# Schematic.net
KiCad netlist of a schematic drawn in Altium Designer
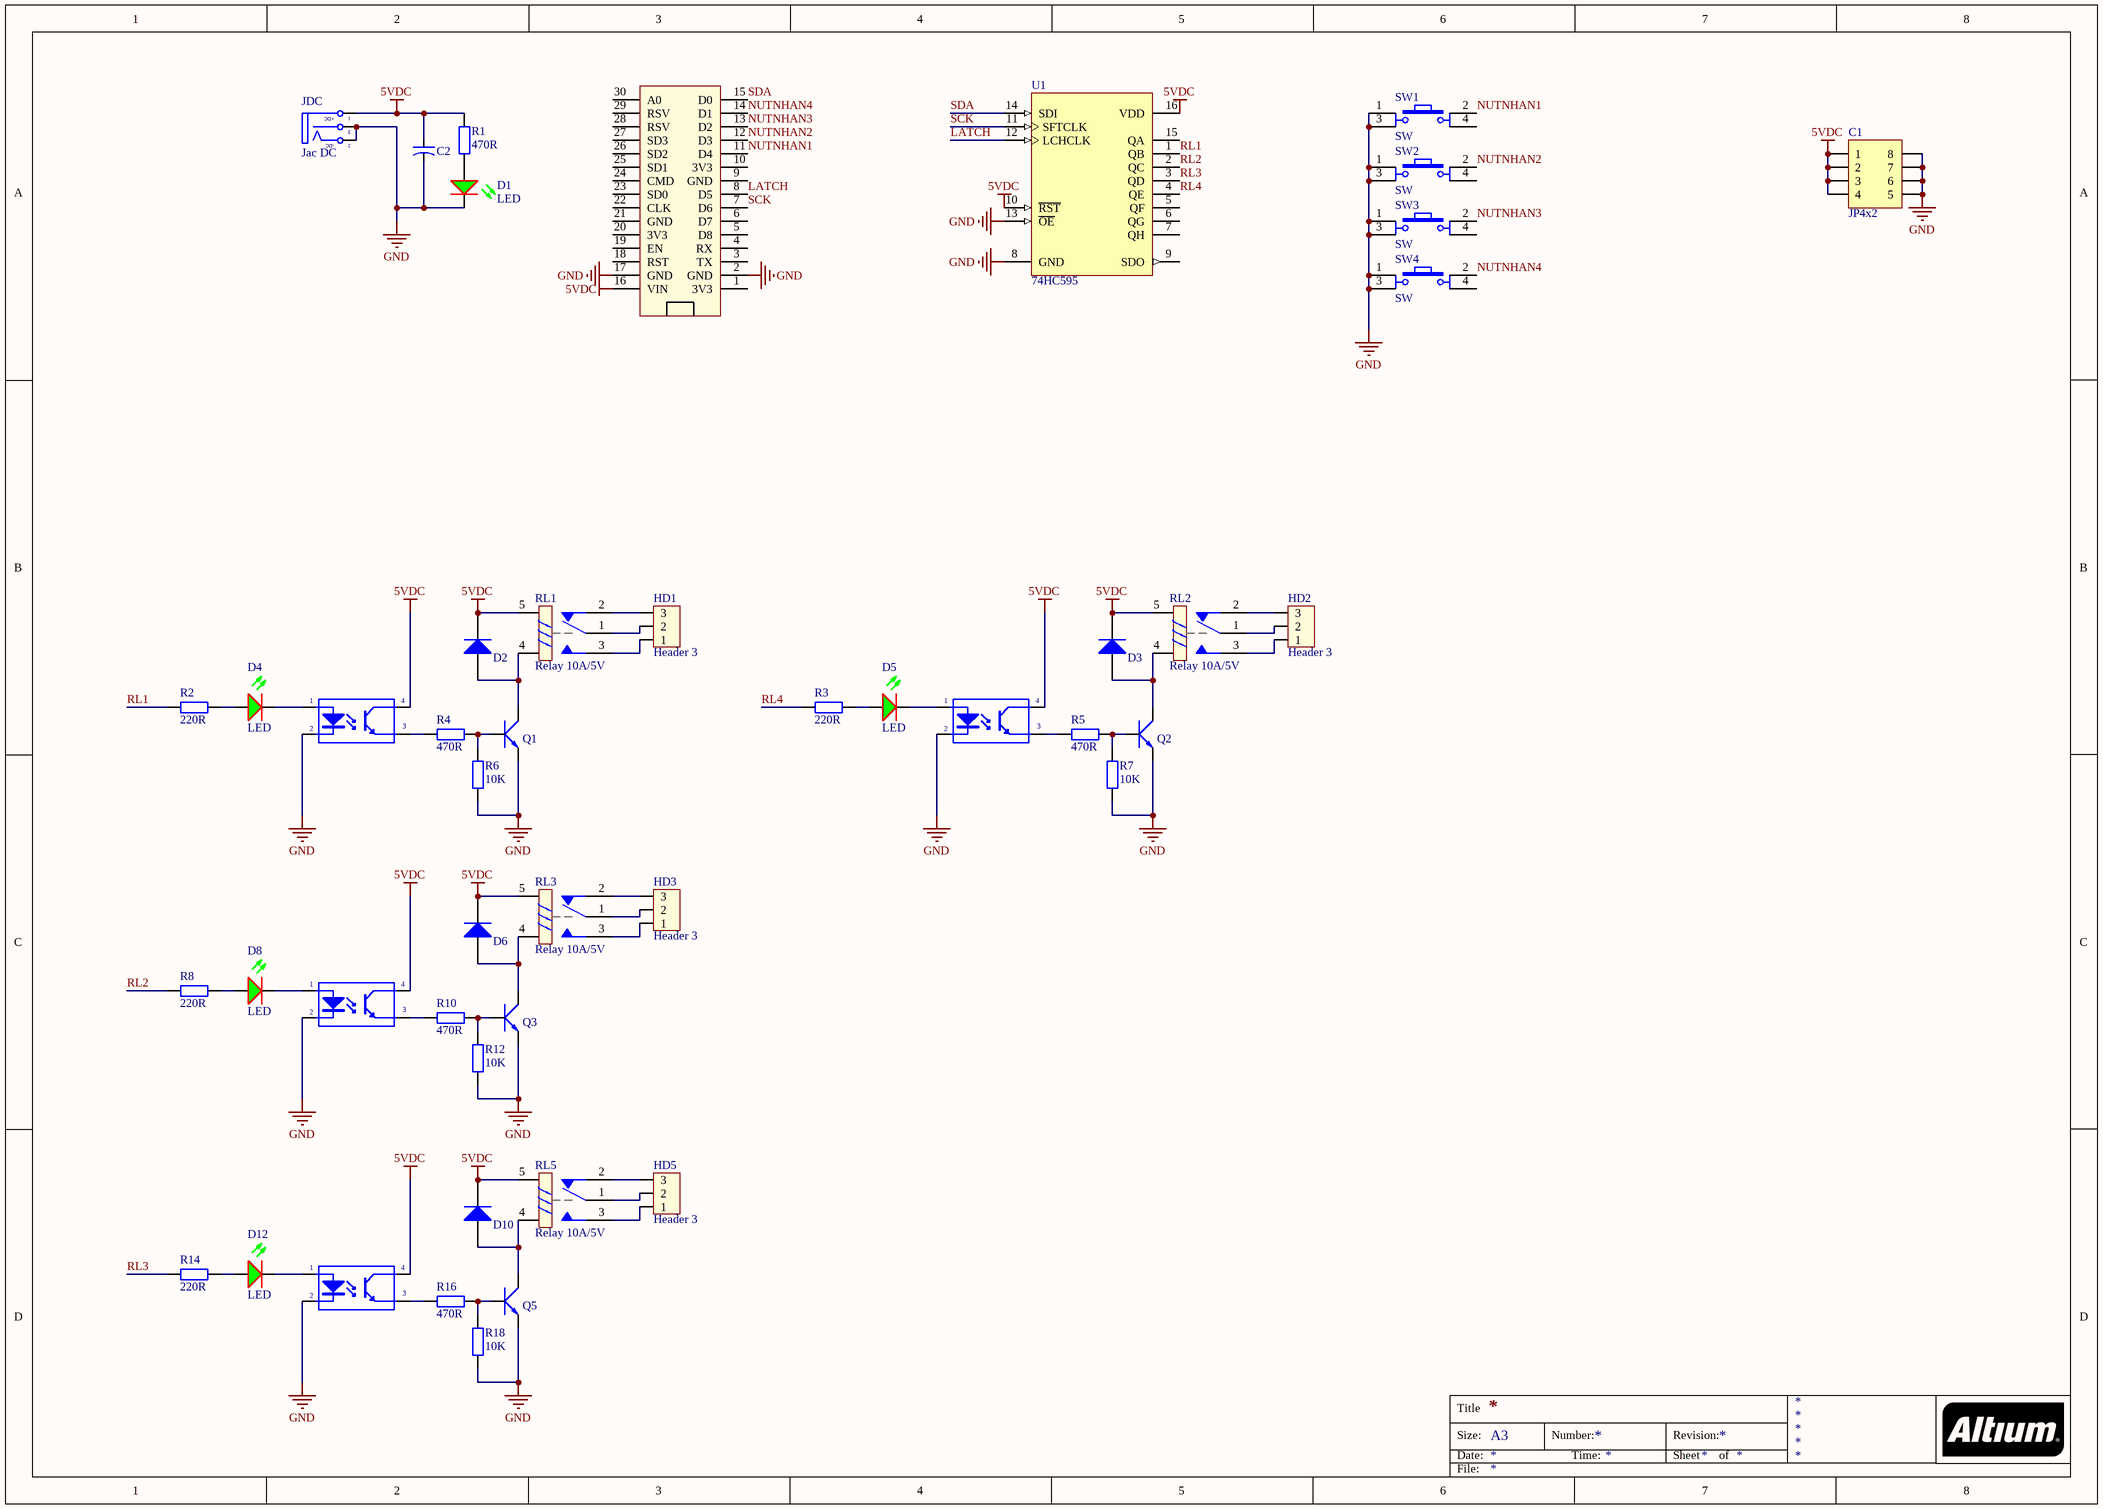
[diagram p0: Schematic.SchDoc]

(export (version "E")
  (design (tool "Eeschema 10.0.6"))
  (components
    (comp (ref "*2")
      (value "Module ESP8266 CP2102")
      (footprint "Module ESP8266 CP2102")
      (libsource (lib "Lib_NTD_HaUI") (part "Module ESP8266 CP2102"))
    )
    (comp (ref "C1")
      (value "JP4x2")
      (footprint "JP4-D2T")
      (description "WR-PHD 2.54 mm Dual Socket Header")
      (fields
        (field (name "MANUFACTURER") "Würth Elektronik eiSos GmbH")
        (field (name "PARTNO") "61300821821")
        (field (name "CREATED BY") "Karrer Zheng")
      )
      (libsource (lib "LIBRARY") (part "JP4x2"))
    )
    (comp (ref "C2")
      (value "10uF")
      (footprint "CA-ALU-2.54")
      (description "Capacitor (Semiconductor SIM Model)")
      (fields (field (name "PUBLISHER") "Altium Limited"))
      (libsource (lib "LIBRARY") (part "CN-ALU-DIP"))
    )
    (comp (ref "D1")
      (value "LED")
      (footprint "LED_SMD_0805")
      (libsource (lib "AltiumLibraryTieuBao") (part "LED"))
    )
    (comp (ref "D2") (value "DIODE") (footprint "DO 214AC") (libsource (lib "Lib_NTD_HaUI") (part "DIODE")))
    (comp (ref "D3") (value "DIODE") (footprint "DO 214AC") (libsource (lib "Lib_NTD_HaUI") (part "DIODE")))
    (comp (ref "D4")
      (value "LED")
      (footprint "LED_SMD_0805")
      (libsource (lib "AltiumLibraryTieuBao") (part "LED"))
    )
    (comp (ref "D5")
      (value "LED")
      (footprint "LED_SMD_0805")
      (libsource (lib "AltiumLibraryTieuBao") (part "LED"))
    )
    (comp (ref "D6") (value "DIODE") (footprint "DO 214AC") (libsource (lib "Lib_NTD_HaUI") (part "DIODE")))
    (comp (ref "D8")
      (value "LED")
      (footprint "LED_SMD_0805")
      (libsource (lib "AltiumLibraryTieuBao") (part "LED"))
    )
    (comp (ref "D10") (value "DIODE") (footprint "DO 214AC") (libsource (lib "Lib_NTD_HaUI") (part "DIODE")))
    (comp (ref "D12")
      (value "LED")
      (footprint "LED_SMD_0805")
      (libsource (lib "AltiumLibraryTieuBao") (part "LED"))
    )
    (comp (ref "HD1")
      (value "Header 3")
      (footprint "HED3")
      (description "Header 3 (Green)")
      (libsource (lib "syhaunguyen") (part "Hed3"))
    )
    (comp (ref "HD2")
      (value "Header 3")
      (footprint "HED3")
      (description "Header 3 (Green)")
      (libsource (lib "syhaunguyen") (part "Hed3"))
    )
    (comp (ref "HD3")
      (value "Header 3")
      (footprint "HED3")
      (description "Header 3 (Green)")
      (libsource (lib "syhaunguyen") (part "Hed3"))
    )
    (comp (ref "HD5")
      (value "Header 3")
      (footprint "HED3")
      (description "Header 3 (Green)")
      (libsource (lib "syhaunguyen") (part "Hed3"))
    )
    (comp (ref "JDC")
      (value "Jac DC")
      (footprint "DC-IN")
      (description "Jac DC input")
      (libsource (lib "syhaunguyen") (part "DCIN"))
    )
    (comp (ref "Q1") (value "C1815") (footprint "SOT23") (libsource (lib "Lib_NTD_HaUI") (part "C1815")))
    (comp (ref "Q2") (value "C1815") (footprint "SOT23") (libsource (lib "Lib_NTD_HaUI") (part "C1815")))
    (comp (ref "Q3") (value "C1815") (footprint "SOT23") (libsource (lib "Lib_NTD_HaUI") (part "C1815")))
    (comp (ref "Q5") (value "C1815") (footprint "SOT23") (libsource (lib "Lib_NTD_HaUI") (part "C1815")))
    (comp (ref "R1")
      (value "470R")
      (footprint "SM-RES-0805")
      (description "Resistor 1/4W")
      (libsource (lib "syhaunguyen") (part "R1/4W"))
    )
    (comp (ref "R2")
      (value "220R")
      (footprint "SM-RES-0805")
      (description "Resistor 1/4W")
      (libsource (lib "syhaunguyen") (part "R1/4W"))
    )
    (comp (ref "R3")
      (value "220R")
      (footprint "SM-RES-0805")
      (description "Resistor 1/4W")
      (libsource (lib "syhaunguyen") (part "R1/4W"))
    )
    (comp (ref "R4")
      (value "470R")
      (footprint "SM-RES-0805")
      (description "Resistor 1/4W")
      (libsource (lib "syhaunguyen") (part "R1/4W"))
    )
    (comp (ref "R5")
      (value "470R")
      (footprint "SM-RES-0805")
      (description "Resistor 1/4W")
      (libsource (lib "syhaunguyen") (part "R1/4W"))
    )
    (comp (ref "R6")
      (value "10K")
      (footprint "SM-RES-0805")
      (description "Resistor 1/4W")
      (libsource (lib "syhaunguyen") (part "R1/4W"))
    )
    (comp (ref "R7")
      (value "10K")
      (footprint "SM-RES-0805")
      (description "Resistor 1/4W")
      (libsource (lib "syhaunguyen") (part "R1/4W"))
    )
    (comp (ref "R8")
      (value "220R")
      (footprint "SM-RES-0805")
      (description "Resistor 1/4W")
      (libsource (lib "syhaunguyen") (part "R1/4W"))
    )
    (comp (ref "R10")
      (value "470R")
      (footprint "SM-RES-0805")
      (description "Resistor 1/4W")
      (libsource (lib "syhaunguyen") (part "R1/4W"))
    )
    (comp (ref "R12")
      (value "10K")
      (footprint "SM-RES-0805")
      (description "Resistor 1/4W")
      (libsource (lib "syhaunguyen") (part "R1/4W"))
    )
    (comp (ref "R14")
      (value "220R")
      (footprint "SM-RES-0805")
      (description "Resistor 1/4W")
      (libsource (lib "syhaunguyen") (part "R1/4W"))
    )
    (comp (ref "R16")
      (value "470R")
      (footprint "SM-RES-0805")
      (description "Resistor 1/4W")
      (libsource (lib "syhaunguyen") (part "R1/4W"))
    )
    (comp (ref "R18")
      (value "10K")
      (footprint "SM-RES-0805")
      (description "Resistor 1/4W")
      (libsource (lib "syhaunguyen") (part "R1/4W"))
    )
    (comp (ref "RL1")
      (value "Relay 10A/5V")
      (footprint "RL_SPDT_10A")
      (description "Relay SPDT,10A - 12VDC 5 Pin")
      (libsource (lib "syhaunguyen") (part "Relay 1"))
    )
    (comp (ref "RL2")
      (value "Relay 10A/5V")
      (footprint "RL_SPDT_10A")
      (description "Relay SPDT,10A - 12VDC 5 Pin")
      (libsource (lib "syhaunguyen") (part "Relay 1"))
    )
    (comp (ref "RL3")
      (value "Relay 10A/5V")
      (footprint "RL_SPDT_10A")
      (description "Relay SPDT,10A - 12VDC 5 Pin")
      (libsource (lib "syhaunguyen") (part "Relay 1"))
    )
    (comp (ref "RL5")
      (value "Relay 10A/5V")
      (footprint "RL_SPDT_10A")
      (description "Relay SPDT,10A - 12VDC 5 Pin")
      (libsource (lib "syhaunguyen") (part "Relay 1"))
    )
    (comp (ref "SW1")
      (value "SW")
      (footprint "SW4B")
      (description "Switch button 4 pin")
      (libsource (lib "syhaunguyen") (part "SW4"))
    )
    (comp (ref "SW2")
      (value "SW")
      (footprint "SW4B")
      (description "Switch button 4 pin")
      (libsource (lib "syhaunguyen") (part "SW4"))
    )
    (comp (ref "SW3")
      (value "SW")
      (footprint "SW4B")
      (description "Switch button 4 pin")
      (libsource (lib "syhaunguyen") (part "SW4"))
    )
    (comp (ref "SW4")
      (value "SW")
      (footprint "SW4B")
      (description "Switch button 4 pin")
      (libsource (lib "syhaunguyen") (part "SW4"))
    )
    (comp (ref "U1")
      (value "74HC595")
      (footprint "SO-16-M")
      (libsource (lib "AltiumLibraryTieuBao") (part "74HC595"))
    )
    (comp (ref "U2") (value "PC817") (footprint "PC817") (libsource (lib "Lib_NTD_HaUI") (part "PC817")))
    (comp (ref "U3") (value "PC817") (footprint "PC817") (libsource (lib "Lib_NTD_HaUI") (part "PC817")))
    (comp (ref "U4") (value "PC817") (footprint "PC817") (libsource (lib "Lib_NTD_HaUI") (part "PC817")))
    (comp (ref "U6") (value "PC817") (footprint "PC817") (libsource (lib "Lib_NTD_HaUI") (part "PC817")))
  )
  (nets
    (net (code "1") (name "/LATCH") (class "Default")
      (node (ref "*2") (pin "8") (pinfunction "D5_8") (pintype "passive"))
      (node (ref "U1") (pin "12") (pinfunction "LCHCLK_12") (pintype "input"))
    )
    (net (code "2") (name "/NUTNHAN1") (class "Default")
      (node (ref "*2") (pin "11") (pinfunction "D4_11") (pintype "passive"))
      (node (ref "SW1") (pin "2") (pintype "passive"))
    )
    (net (code "3") (name "/NUTNHAN2") (class "Default")
      (node (ref "*2") (pin "12") (pinfunction "D3_12") (pintype "passive"))
      (node (ref "SW2") (pin "2") (pintype "passive"))
    )
    (net (code "4") (name "/NUTNHAN3") (class "Default")
      (node (ref "*2") (pin "13") (pinfunction "D2_13") (pintype "passive"))
      (node (ref "SW3") (pin "2") (pintype "passive"))
    )
    (net (code "5") (name "/NUTNHAN4") (class "Default")
      (node (ref "*2") (pin "14") (pinfunction "D1_14") (pintype "passive"))
      (node (ref "SW4") (pin "2") (pintype "passive"))
    )
    (net (code "6") (name "/RL1") (class "Default")
      (node (ref "R2") (pin "1") (pinfunction "1_1") (pintype "passive"))
      (node (ref "U1") (pin "1") (pinfunction "QB_1") (pintype "tri_state"))
    )
    (net (code "7") (name "/RL2") (class "Default")
      (node (ref "R8") (pin "1") (pinfunction "1_1") (pintype "passive"))
      (node (ref "U1") (pin "2") (pinfunction "QC_2") (pintype "tri_state"))
    )
    (net (code "8") (name "/RL3") (class "Default")
      (node (ref "R14") (pin "1") (pinfunction "1_1") (pintype "passive"))
      (node (ref "U1") (pin "3") (pinfunction "QD_3") (pintype "tri_state"))
    )
    (net (code "9") (name "/RL4") (class "Default")
      (node (ref "R3") (pin "1") (pinfunction "1_1") (pintype "passive"))
      (node (ref "U1") (pin "4") (pinfunction "QE_4") (pintype "tri_state"))
    )
    (net (code "10") (name "/SCK") (class "Default")
      (node (ref "*2") (pin "7") (pinfunction "D6_7") (pintype "passive"))
      (node (ref "U1") (pin "11") (pinfunction "SFTCLK_11") (pintype "input"))
    )
    (net (code "11") (name "/SDA") (class "Default")
      (node (ref "*2") (pin "15") (pinfunction "D0_15") (pintype "passive"))
      (node (ref "U1") (pin "14") (pinfunction "SDI_14") (pintype "input"))
    )
    (net (code "12") (name "5VDC") (class "Default")
      (node (ref "*2") (pin "16") (pinfunction "VIN_16") (pintype "passive"))
      (node (ref "C1") (pin "1") (pinfunction "1_1") (pintype "passive"))
      (node (ref "C1") (pin "2") (pinfunction "2_2") (pintype "passive"))
      (node (ref "C1") (pin "3") (pinfunction "3_3") (pintype "passive"))
      (node (ref "C1") (pin "4") (pinfunction "4_4") (pintype "passive"))
      (node (ref "C2") (pin "1") (pinfunction "1_1") (pintype "passive"))
      (node (ref "D10") (pin "2") (pinfunction "K_2") (pintype "passive"))
      (node (ref "D2") (pin "2") (pinfunction "K_2") (pintype "passive"))
      (node (ref "D3") (pin "2") (pinfunction "K_2") (pintype "passive"))
      (node (ref "D6") (pin "2") (pinfunction "K_2") (pintype "passive"))
      (node (ref "JDC") (pin "1") (pinfunction "T_1") (pintype "passive"))
      (node (ref "R1") (pin "2") (pinfunction "2_2") (pintype "passive"))
      (node (ref "RL1") (pin "5") (pinfunction "5_5") (pintype "passive"))
      (node (ref "RL2") (pin "5") (pinfunction "5_5") (pintype "passive"))
      (node (ref "RL3") (pin "5") (pinfunction "5_5") (pintype "passive"))
      (node (ref "RL5") (pin "5") (pinfunction "5_5") (pintype "passive"))
      (node (ref "U1") (pin "10") (pinfunction "~{RST}_10") (pintype "input"))
      (node (ref "U1") (pin "16") (pinfunction "VDD_16") (pintype "power_in"))
      (node (ref "U2") (pin "4") (pinfunction "C_4") (pintype "passive"))
      (node (ref "U3") (pin "4") (pinfunction "C_4") (pintype "passive"))
      (node (ref "U4") (pin "4") (pinfunction "C_4") (pintype "passive"))
      (node (ref "U6") (pin "4") (pinfunction "C_4") (pintype "passive"))
    )
    (net (code "13") (name "GND") (class "Default")
      (node (ref "*2") (pin "17") (pinfunction "GND_17") (pintype "passive"))
      (node (ref "*2") (pin "2") (pinfunction "GND_2") (pintype "passive"))
      (node (ref "C1") (pin "5") (pinfunction "5_5") (pintype "passive"))
      (node (ref "C1") (pin "6") (pinfunction "6_6") (pintype "passive"))
      (node (ref "C1") (pin "7") (pinfunction "7_7") (pintype "passive"))
      (node (ref "C1") (pin "8") (pinfunction "8_8") (pintype "passive"))
      (node (ref "C2") (pin "2") (pinfunction "2_2") (pintype "passive"))
      (node (ref "D1") (pin "2") (pinfunction "K_2") (pintype "passive"))
      (node (ref "JDC") (pin "2") (pinfunction "TN_2") (pintype "passive"))
      (node (ref "JDC") (pin "3") (pinfunction "S_3") (pintype "power_in"))
      (node (ref "Q1") (pin "2") (pinfunction "E_2") (pintype "passive"))
      (node (ref "Q2") (pin "2") (pinfunction "E_2") (pintype "passive"))
      (node (ref "Q3") (pin "2") (pinfunction "E_2") (pintype "passive"))
      (node (ref "Q5") (pin "2") (pinfunction "E_2") (pintype "passive"))
      (node (ref "R12") (pin "1") (pinfunction "1_1") (pintype "passive"))
      (node (ref "R18") (pin "1") (pinfunction "1_1") (pintype "passive"))
      (node (ref "R6") (pin "1") (pinfunction "1_1") (pintype "passive"))
      (node (ref "R7") (pin "1") (pinfunction "1_1") (pintype "passive"))
      (node (ref "SW1") (pin "1") (pintype "passive"))
      (node (ref "SW1") (pin "3") (pintype "passive"))
      (node (ref "SW2") (pin "1") (pintype "passive"))
      (node (ref "SW2") (pin "3") (pintype "passive"))
      (node (ref "SW3") (pin "1") (pintype "passive"))
      (node (ref "SW3") (pin "3") (pintype "passive"))
      (node (ref "SW4") (pin "1") (pintype "passive"))
      (node (ref "SW4") (pin "3") (pintype "passive"))
      (node (ref "U1") (pin "13") (pinfunction "~{OE}_13") (pintype "input"))
      (node (ref "U1") (pin "8") (pinfunction "GND_8") (pintype "power_in"))
      (node (ref "U2") (pin "2") (pinfunction "K_2") (pintype "passive"))
      (node (ref "U3") (pin "2") (pinfunction "K_2") (pintype "passive"))
      (node (ref "U4") (pin "2") (pinfunction "K_2") (pintype "passive"))
      (node (ref "U6") (pin "2") (pinfunction "K_2") (pintype "passive"))
    )
    (net (code "14") (name "Net-(D1-A)") (class "Default")
      (node (ref "D1") (pin "1") (pinfunction "A_1") (pintype "passive"))
      (node (ref "R1") (pin "1") (pinfunction "1_1") (pintype "passive"))
    )
    (net (code "15") (name "Net-(D2-A)") (class "Default")
      (node (ref "D2") (pin "1") (pinfunction "A_1") (pintype "passive"))
      (node (ref "Q1") (pin "3") (pinfunction "C_3") (pintype "passive"))
      (node (ref "RL1") (pin "4") (pinfunction "4_4") (pintype "passive"))
    )
    (net (code "16") (name "Net-(D3-A)") (class "Default")
      (node (ref "D3") (pin "1") (pinfunction "A_1") (pintype "passive"))
      (node (ref "Q2") (pin "3") (pinfunction "C_3") (pintype "passive"))
      (node (ref "RL2") (pin "4") (pinfunction "4_4") (pintype "passive"))
    )
    (net (code "17") (name "Net-(D4-A)") (class "Default")
      (node (ref "D4") (pin "1") (pinfunction "A_1") (pintype "passive"))
      (node (ref "R2") (pin "2") (pinfunction "2_2") (pintype "passive"))
    )
    (net (code "18") (name "Net-(D4-K)") (class "Default")
      (node (ref "D4") (pin "2") (pinfunction "K_2") (pintype "passive"))
      (node (ref "U2") (pin "1") (pinfunction "A_1") (pintype "passive"))
    )
    (net (code "19") (name "Net-(D5-A)") (class "Default")
      (node (ref "D5") (pin "1") (pinfunction "A_1") (pintype "passive"))
      (node (ref "R3") (pin "2") (pinfunction "2_2") (pintype "passive"))
    )
    (net (code "20") (name "Net-(D5-K)") (class "Default")
      (node (ref "D5") (pin "2") (pinfunction "K_2") (pintype "passive"))
      (node (ref "U3") (pin "1") (pinfunction "A_1") (pintype "passive"))
    )
    (net (code "21") (name "Net-(D6-A)") (class "Default")
      (node (ref "D6") (pin "1") (pinfunction "A_1") (pintype "passive"))
      (node (ref "Q3") (pin "3") (pinfunction "C_3") (pintype "passive"))
      (node (ref "RL3") (pin "4") (pinfunction "4_4") (pintype "passive"))
    )
    (net (code "22") (name "Net-(D8-A)") (class "Default")
      (node (ref "D8") (pin "1") (pinfunction "A_1") (pintype "passive"))
      (node (ref "R8") (pin "2") (pinfunction "2_2") (pintype "passive"))
    )
    (net (code "23") (name "Net-(D8-K)") (class "Default")
      (node (ref "D8") (pin "2") (pinfunction "K_2") (pintype "passive"))
      (node (ref "U4") (pin "1") (pinfunction "A_1") (pintype "passive"))
    )
    (net (code "24") (name "Net-(D10-A)") (class "Default")
      (node (ref "D10") (pin "1") (pinfunction "A_1") (pintype "passive"))
      (node (ref "Q5") (pin "3") (pinfunction "C_3") (pintype "passive"))
      (node (ref "RL5") (pin "4") (pinfunction "4_4") (pintype "passive"))
    )
    (net (code "25") (name "Net-(D12-A)") (class "Default")
      (node (ref "D12") (pin "1") (pinfunction "A_1") (pintype "passive"))
      (node (ref "R14") (pin "2") (pinfunction "2_2") (pintype "passive"))
    )
    (net (code "26") (name "Net-(D12-K)") (class "Default")
      (node (ref "D12") (pin "2") (pinfunction "K_2") (pintype "passive"))
      (node (ref "U6") (pin "1") (pinfunction "A_1") (pintype "passive"))
    )
    (net (code "27") (name "Net-(HD1-Pad1)") (class "Default")
      (node (ref "HD1") (pin "1") (pinfunction "1_1") (pintype "passive"))
      (node (ref "RL1") (pin "3") (pinfunction "3_3") (pintype "passive"))
    )
    (net (code "28") (name "Net-(HD1-Pad2)") (class "Default")
      (node (ref "HD1") (pin "2") (pinfunction "2_2") (pintype "passive"))
      (node (ref "RL1") (pin "1") (pinfunction "1_1") (pintype "passive"))
    )
    (net (code "29") (name "Net-(HD1-Pad3)") (class "Default")
      (node (ref "HD1") (pin "3") (pinfunction "3_3") (pintype "passive"))
      (node (ref "RL1") (pin "2") (pinfunction "2_2") (pintype "passive"))
    )
    (net (code "30") (name "Net-(HD2-Pad1)") (class "Default")
      (node (ref "HD2") (pin "1") (pinfunction "1_1") (pintype "passive"))
      (node (ref "RL2") (pin "3") (pinfunction "3_3") (pintype "passive"))
    )
    (net (code "31") (name "Net-(HD2-Pad2)") (class "Default")
      (node (ref "HD2") (pin "2") (pinfunction "2_2") (pintype "passive"))
      (node (ref "RL2") (pin "1") (pinfunction "1_1") (pintype "passive"))
    )
    (net (code "32") (name "Net-(HD2-Pad3)") (class "Default")
      (node (ref "HD2") (pin "3") (pinfunction "3_3") (pintype "passive"))
      (node (ref "RL2") (pin "2") (pinfunction "2_2") (pintype "passive"))
    )
    (net (code "33") (name "Net-(HD3-Pad1)") (class "Default")
      (node (ref "HD3") (pin "1") (pinfunction "1_1") (pintype "passive"))
      (node (ref "RL3") (pin "3") (pinfunction "3_3") (pintype "passive"))
    )
    (net (code "34") (name "Net-(HD3-Pad2)") (class "Default")
      (node (ref "HD3") (pin "2") (pinfunction "2_2") (pintype "passive"))
      (node (ref "RL3") (pin "1") (pinfunction "1_1") (pintype "passive"))
    )
    (net (code "35") (name "Net-(HD3-Pad3)") (class "Default")
      (node (ref "HD3") (pin "3") (pinfunction "3_3") (pintype "passive"))
      (node (ref "RL3") (pin "2") (pinfunction "2_2") (pintype "passive"))
    )
    (net (code "36") (name "Net-(HD5-Pad1)") (class "Default")
      (node (ref "HD5") (pin "1") (pinfunction "1_1") (pintype "passive"))
      (node (ref "RL5") (pin "3") (pinfunction "3_3") (pintype "passive"))
    )
    (net (code "37") (name "Net-(HD5-Pad2)") (class "Default")
      (node (ref "HD5") (pin "2") (pinfunction "2_2") (pintype "passive"))
      (node (ref "RL5") (pin "1") (pinfunction "1_1") (pintype "passive"))
    )
    (net (code "38") (name "Net-(HD5-Pad3)") (class "Default")
      (node (ref "HD5") (pin "3") (pinfunction "3_3") (pintype "passive"))
      (node (ref "RL5") (pin "2") (pinfunction "2_2") (pintype "passive"))
    )
    (net (code "39") (name "Net-(Q1-B)") (class "Default")
      (node (ref "Q1") (pin "1") (pinfunction "B_1") (pintype "passive"))
      (node (ref "R4") (pin "2") (pinfunction "2_2") (pintype "passive"))
      (node (ref "R6") (pin "2") (pinfunction "2_2") (pintype "passive"))
    )
    (net (code "40") (name "Net-(Q2-B)") (class "Default")
      (node (ref "Q2") (pin "1") (pinfunction "B_1") (pintype "passive"))
      (node (ref "R5") (pin "2") (pinfunction "2_2") (pintype "passive"))
      (node (ref "R7") (pin "2") (pinfunction "2_2") (pintype "passive"))
    )
    (net (code "41") (name "Net-(Q3-B)") (class "Default")
      (node (ref "Q3") (pin "1") (pinfunction "B_1") (pintype "passive"))
      (node (ref "R10") (pin "2") (pinfunction "2_2") (pintype "passive"))
      (node (ref "R12") (pin "2") (pinfunction "2_2") (pintype "passive"))
    )
    (net (code "42") (name "Net-(Q5-B)") (class "Default")
      (node (ref "Q5") (pin "1") (pinfunction "B_1") (pintype "passive"))
      (node (ref "R16") (pin "2") (pinfunction "2_2") (pintype "passive"))
      (node (ref "R18") (pin "2") (pinfunction "2_2") (pintype "passive"))
    )
    (net (code "43") (name "Net-(U2-E)") (class "Default")
      (node (ref "R4") (pin "1") (pinfunction "1_1") (pintype "passive"))
      (node (ref "U2") (pin "3") (pinfunction "E_3") (pintype "passive"))
    )
    (net (code "44") (name "Net-(U3-E)") (class "Default")
      (node (ref "R5") (pin "1") (pinfunction "1_1") (pintype "passive"))
      (node (ref "U3") (pin "3") (pinfunction "E_3") (pintype "passive"))
    )
    (net (code "45") (name "Net-(U4-E)") (class "Default")
      (node (ref "R10") (pin "1") (pinfunction "1_1") (pintype "passive"))
      (node (ref "U4") (pin "3") (pinfunction "E_3") (pintype "passive"))
    )
    (net (code "46") (name "Net-(U6-E)") (class "Default")
      (node (ref "R16") (pin "1") (pinfunction "1_1") (pintype "passive"))
      (node (ref "U6") (pin "3") (pinfunction "E_3") (pintype "passive"))
    )
    (net (code "47") (name "unconnected-(*2-3V3-Pad1)") (class "Default")
      (node (ref "*2") (pin "1") (pinfunction "3V3_1") (pintype "passive"))
    )
    (net (code "48") (name "unconnected-(*2-3V3-Pad10)") (class "Default")
      (node (ref "*2") (pin "10") (pinfunction "3V3_10") (pintype "passive"))
    )
    (net (code "49") (name "unconnected-(*2-3V3-Pad20)") (class "Default")
      (node (ref "*2") (pin "20") (pinfunction "3V3_20") (pintype "passive"))
    )
    (net (code "50") (name "unconnected-(*2-A0-Pad30)") (class "Default")
      (node (ref "*2") (pin "30") (pinfunction "A0_30") (pintype "passive"))
    )
    (net (code "51") (name "unconnected-(*2-CLK-Pad22)") (class "Default")
      (node (ref "*2") (pin "22") (pinfunction "CLK_22") (pintype "passive"))
    )
    (net (code "52") (name "unconnected-(*2-CMD-Pad24)") (class "Default")
      (node (ref "*2") (pin "24") (pinfunction "CMD_24") (pintype "passive"))
    )
    (net (code "53") (name "unconnected-(*2-D7-Pad6)") (class "Default")
      (node (ref "*2") (pin "6") (pinfunction "D7_6") (pintype "passive"))
    )
    (net (code "54") (name "unconnected-(*2-D8-Pad5)") (class "Default")
      (node (ref "*2") (pin "5") (pinfunction "D8_5") (pintype "passive"))
    )
    (net (code "55") (name "unconnected-(*2-EN-Pad19)") (class "Default")
      (node (ref "*2") (pin "19") (pinfunction "EN_19") (pintype "passive"))
    )
    (net (code "56") (name "unconnected-(*2-GND-Pad9)") (class "Default")
      (node (ref "*2") (pin "9") (pinfunction "GND_9") (pintype "passive"))
    )
    (net (code "57") (name "unconnected-(*2-GND-Pad21)") (class "Default")
      (node (ref "*2") (pin "21") (pinfunction "GND_21") (pintype "passive"))
    )
    (net (code "58") (name "unconnected-(*2-RST-Pad18)") (class "Default")
      (node (ref "*2") (pin "18") (pinfunction "RST_18") (pintype "passive"))
    )
    (net (code "59") (name "unconnected-(*2-RSV-Pad28)") (class "Default")
      (node (ref "*2") (pin "28") (pinfunction "RSV_28") (pintype "passive"))
    )
    (net (code "60") (name "unconnected-(*2-RSV-Pad29)") (class "Default")
      (node (ref "*2") (pin "29") (pinfunction "RSV_29") (pintype "passive"))
    )
    (net (code "61") (name "unconnected-(*2-RX-Pad4)") (class "Default")
      (node (ref "*2") (pin "4") (pinfunction "RX_4") (pintype "passive"))
    )
    (net (code "62") (name "unconnected-(*2-SD0-Pad23)") (class "Default")
      (node (ref "*2") (pin "23") (pinfunction "SD0_23") (pintype "passive"))
    )
    (net (code "63") (name "unconnected-(*2-SD1-Pad25)") (class "Default")
      (node (ref "*2") (pin "25") (pinfunction "SD1_25") (pintype "passive"))
    )
    (net (code "64") (name "unconnected-(*2-SD2-Pad26)") (class "Default")
      (node (ref "*2") (pin "26") (pinfunction "SD2_26") (pintype "passive"))
    )
    (net (code "65") (name "unconnected-(*2-SD3-Pad27)") (class "Default")
      (node (ref "*2") (pin "27") (pinfunction "SD3_27") (pintype "passive"))
    )
    (net (code "66") (name "unconnected-(*2-TX-Pad3)") (class "Default")
      (node (ref "*2") (pin "3") (pinfunction "TX_3") (pintype "passive"))
    )
    (net (code "67") (name "unconnected-(SW1-Pad4)") (class "Default")
      (node (ref "SW1") (pin "4") (pintype "passive"))
    )
    (net (code "68") (name "unconnected-(SW2-Pad4)") (class "Default")
      (node (ref "SW2") (pin "4") (pintype "passive"))
    )
    (net (code "69") (name "unconnected-(SW3-Pad4)") (class "Default")
      (node (ref "SW3") (pin "4") (pintype "passive"))
    )
    (net (code "70") (name "unconnected-(SW4-Pad4)") (class "Default")
      (node (ref "SW4") (pin "4") (pintype "passive"))
    )
    (net (code "71") (name "unconnected-(U1-QA-Pad15)") (class "Default")
      (node (ref "U1") (pin "15") (pinfunction "QA_15") (pintype "tri_state"))
    )
    (net (code "72") (name "unconnected-(U1-QF-Pad5)") (class "Default")
      (node (ref "U1") (pin "5") (pinfunction "QF_5") (pintype "tri_state"))
    )
    (net (code "73") (name "unconnected-(U1-QG-Pad6)") (class "Default")
      (node (ref "U1") (pin "6") (pinfunction "QG_6") (pintype "tri_state"))
    )
    (net (code "74") (name "unconnected-(U1-QH-Pad7)") (class "Default")
      (node (ref "U1") (pin "7") (pinfunction "QH_7") (pintype "tri_state"))
    )
    (net (code "75") (name "unconnected-(U1-SDO-Pad9)") (class "Default")
      (node (ref "U1") (pin "9") (pinfunction "SDO_9") (pintype "output"))
    )
  )
)
